# CheetahBooster.net
KiCad netlist of a schematic drawn in EAGLE
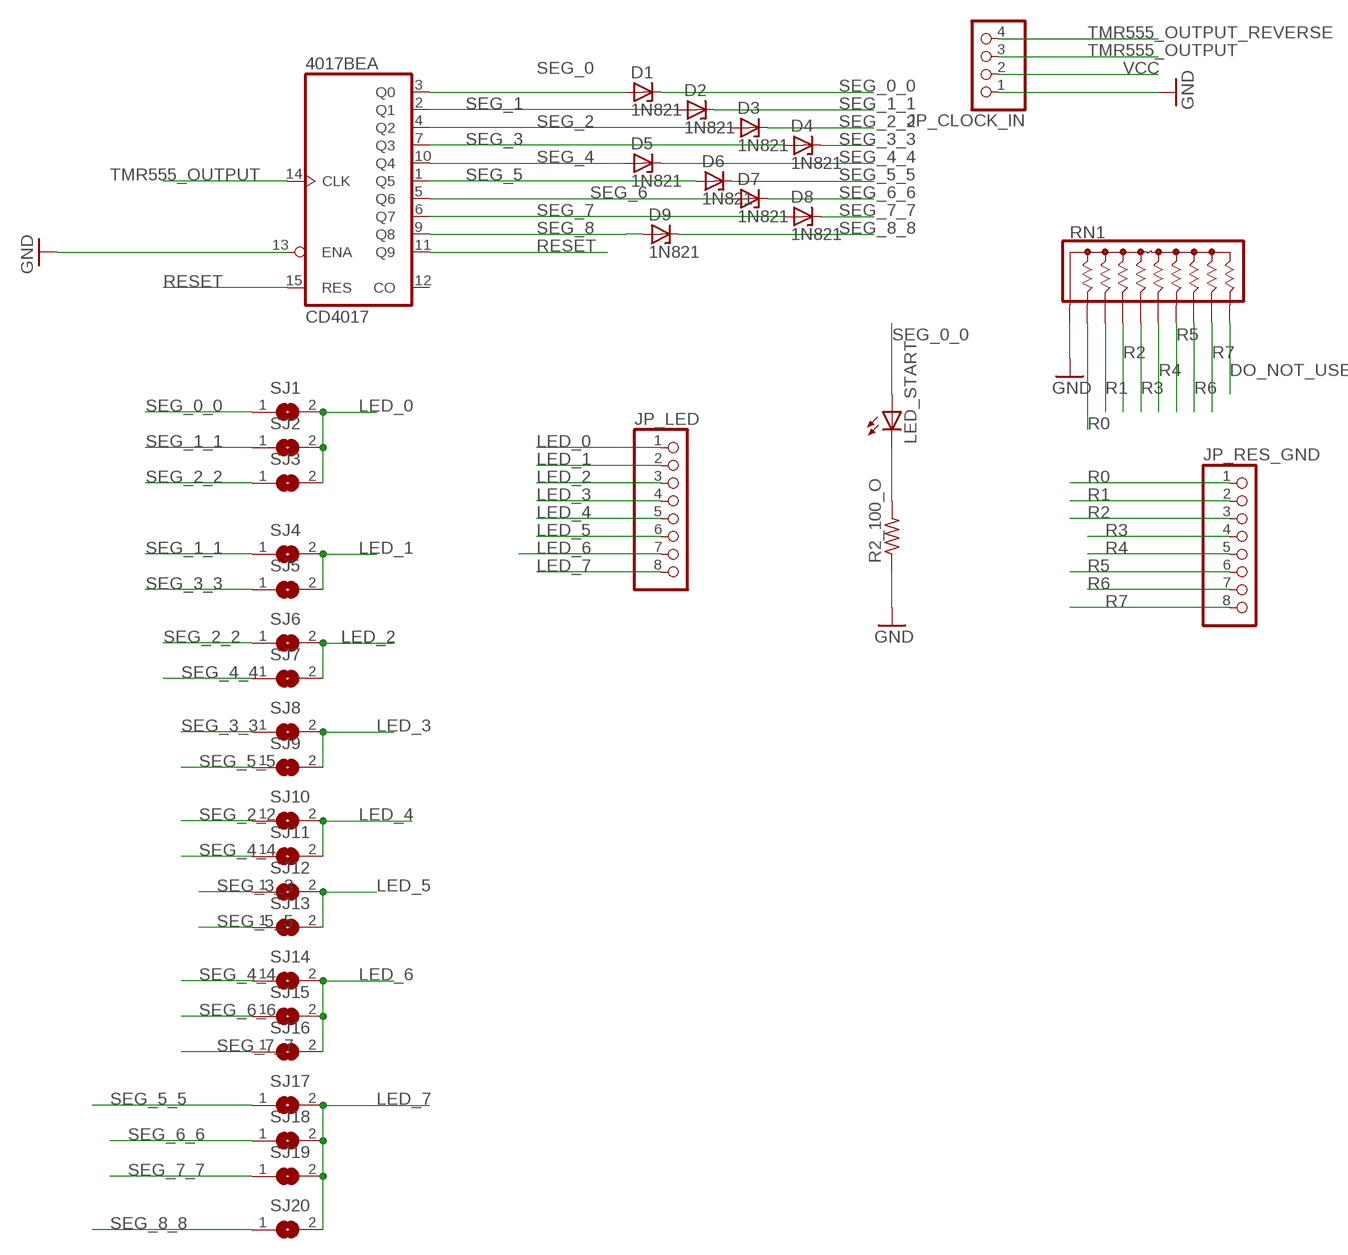
[diagram p0: schematic, sheet 1]

(export (version "E")
  (design (tool "Eeschema 10.0.6"))
  (components
    (comp (ref "4017BE")
      (value "CD4017")
      (footprint "eagle-import:DIL16")
      (libsource (lib "eagle-import") (part "CD4017"))
    )
    (comp (ref "D1")
      (value "1N821")
      (footprint "eagle-import:DO35Z10")
      (libsource (lib "eagle-import") (part "1N821"))
    )
    (comp (ref "D2")
      (value "1N821")
      (footprint "eagle-import:DO35Z10")
      (libsource (lib "eagle-import") (part "1N821"))
    )
    (comp (ref "D3")
      (value "1N821")
      (footprint "eagle-import:DO35Z10")
      (libsource (lib "eagle-import") (part "1N821"))
    )
    (comp (ref "D4")
      (value "1N821")
      (footprint "eagle-import:DO35Z10")
      (libsource (lib "eagle-import") (part "1N821"))
    )
    (comp (ref "D5")
      (value "1N821")
      (footprint "eagle-import:DO35Z10")
      (libsource (lib "eagle-import") (part "1N821"))
    )
    (comp (ref "D6")
      (value "1N821")
      (footprint "eagle-import:DO35Z10")
      (libsource (lib "eagle-import") (part "1N821"))
    )
    (comp (ref "D7")
      (value "1N821")
      (footprint "eagle-import:DO35Z10")
      (libsource (lib "eagle-import") (part "1N821"))
    )
    (comp (ref "D8")
      (value "1N821")
      (footprint "eagle-import:DO35Z10")
      (libsource (lib "eagle-import") (part "1N821"))
    )
    (comp (ref "D9")
      (value "1N821")
      (footprint "eagle-import:DO35Z10")
      (libsource (lib "eagle-import") (part "1N821"))
    )
    (comp (ref "JP_CLOCK_IN")
      (value "PINHD-1X4")
      (footprint "eagle-import:1X04")
      (libsource (lib "eagle-import") (part "PINHD-1X4"))
    )
    (comp (ref "JP_LED")
      (value "PINHD-1X8")
      (footprint "eagle-import:1X08")
      (libsource (lib "eagle-import") (part "PINHD-1X8"))
    )
    (comp (ref "JP_RES_GND")
      (value "PINHD-1X8")
      (footprint "eagle-import:1X08")
      (libsource (lib "eagle-import") (part "PINHD-1X8"))
    )
    (comp (ref "LED_START")
      (value "LEDSMT1206")
      (footprint "eagle-import:1206")
      (libsource (lib "eagle-import") (part "LEDSMT1206"))
    )
    (comp (ref "R2_100_O")
      (value "R-US_R1206")
      (footprint "eagle-import:R1206")
      (libsource (lib "eagle-import") (part "R-US_R1206"))
    )
    (comp (ref "RN1")
      (value "4610X")
      (footprint "eagle-import:SIP10")
      (libsource (lib "eagle-import") (part "4610X"))
    )
    (comp (ref "SJ1")
      (value "SOLDERJUMPER")
      (footprint "eagle-import:SOLDERJUMPER_ARROW_NOPASTE")
      (libsource (lib "eagle-import") (part "SOLDERJUMPER"))
    )
    (comp (ref "SJ2")
      (value "SOLDERJUMPER")
      (footprint "eagle-import:SOLDERJUMPER_ARROW_NOPASTE")
      (libsource (lib "eagle-import") (part "SOLDERJUMPER"))
    )
    (comp (ref "SJ3")
      (value "SOLDERJUMPER")
      (footprint "eagle-import:SOLDERJUMPER_ARROW_NOPASTE")
      (libsource (lib "eagle-import") (part "SOLDERJUMPER"))
    )
    (comp (ref "SJ4")
      (value "SOLDERJUMPER")
      (footprint "eagle-import:SOLDERJUMPER_ARROW_NOPASTE")
      (libsource (lib "eagle-import") (part "SOLDERJUMPER"))
    )
    (comp (ref "SJ5")
      (value "SOLDERJUMPER")
      (footprint "eagle-import:SOLDERJUMPER_ARROW_NOPASTE")
      (libsource (lib "eagle-import") (part "SOLDERJUMPER"))
    )
    (comp (ref "SJ6")
      (value "SOLDERJUMPER")
      (footprint "eagle-import:SOLDERJUMPER_ARROW_NOPASTE")
      (libsource (lib "eagle-import") (part "SOLDERJUMPER"))
    )
    (comp (ref "SJ7")
      (value "SOLDERJUMPER")
      (footprint "eagle-import:SOLDERJUMPER_ARROW_NOPASTE")
      (libsource (lib "eagle-import") (part "SOLDERJUMPER"))
    )
    (comp (ref "SJ8")
      (value "SOLDERJUMPER")
      (footprint "eagle-import:SOLDERJUMPER_ARROW_NOPASTE")
      (libsource (lib "eagle-import") (part "SOLDERJUMPER"))
    )
    (comp (ref "SJ9")
      (value "SOLDERJUMPER")
      (footprint "eagle-import:SOLDERJUMPER_ARROW_NOPASTE")
      (libsource (lib "eagle-import") (part "SOLDERJUMPER"))
    )
    (comp (ref "SJ10")
      (value "SOLDERJUMPER")
      (footprint "eagle-import:SOLDERJUMPER_ARROW_NOPASTE")
      (libsource (lib "eagle-import") (part "SOLDERJUMPER"))
    )
    (comp (ref "SJ11")
      (value "SOLDERJUMPER")
      (footprint "eagle-import:SOLDERJUMPER_ARROW_NOPASTE")
      (libsource (lib "eagle-import") (part "SOLDERJUMPER"))
    )
    (comp (ref "SJ12")
      (value "SOLDERJUMPER")
      (footprint "eagle-import:SOLDERJUMPER_ARROW_NOPASTE")
      (libsource (lib "eagle-import") (part "SOLDERJUMPER"))
    )
    (comp (ref "SJ13")
      (value "SOLDERJUMPER")
      (footprint "eagle-import:SOLDERJUMPER_ARROW_NOPASTE")
      (libsource (lib "eagle-import") (part "SOLDERJUMPER"))
    )
    (comp (ref "SJ14")
      (value "SOLDERJUMPER")
      (footprint "eagle-import:SOLDERJUMPER_ARROW_NOPASTE")
      (libsource (lib "eagle-import") (part "SOLDERJUMPER"))
    )
    (comp (ref "SJ15")
      (value "SOLDERJUMPER")
      (footprint "eagle-import:SOLDERJUMPER_ARROW_NOPASTE")
      (libsource (lib "eagle-import") (part "SOLDERJUMPER"))
    )
    (comp (ref "SJ16")
      (value "SOLDERJUMPER")
      (footprint "eagle-import:SOLDERJUMPER_ARROW_NOPASTE")
      (libsource (lib "eagle-import") (part "SOLDERJUMPER"))
    )
    (comp (ref "SJ17")
      (value "SOLDERJUMPER")
      (footprint "eagle-import:SOLDERJUMPER_ARROW_NOPASTE")
      (libsource (lib "eagle-import") (part "SOLDERJUMPER"))
    )
    (comp (ref "SJ18")
      (value "SOLDERJUMPER")
      (footprint "eagle-import:SOLDERJUMPER_ARROW_NOPASTE")
      (libsource (lib "eagle-import") (part "SOLDERJUMPER"))
    )
    (comp (ref "SJ19")
      (value "SOLDERJUMPER")
      (footprint "eagle-import:SOLDERJUMPER_ARROW_NOPASTE")
      (libsource (lib "eagle-import") (part "SOLDERJUMPER"))
    )
    (comp (ref "SJ20")
      (value "SOLDERJUMPER")
      (footprint "eagle-import:SOLDERJUMPER_ARROW_NOPASTE")
      (libsource (lib "eagle-import") (part "SOLDERJUMPER"))
    )
  )
  (nets
    (net (code "1") (name "/DO_NOT_USE") (class "Default")
      (node (ref "RN1") (pin "10") (pinfunction "10_10") (pintype "passive"))
    )
    (net (code "2") (name "/LED_0") (class "Default")
      (node (ref "JP_LED") (pin "1") (pinfunction "1_1") (pintype "passive"))
      (node (ref "SJ1") (pin "2") (pinfunction "2_2") (pintype "passive"))
      (node (ref "SJ2") (pin "2") (pinfunction "2_2") (pintype "passive"))
      (node (ref "SJ3") (pin "2") (pinfunction "2_2") (pintype "passive"))
    )
    (net (code "3") (name "/LED_1") (class "Default")
      (node (ref "JP_LED") (pin "2") (pinfunction "2_2") (pintype "passive"))
      (node (ref "SJ4") (pin "2") (pinfunction "2_2") (pintype "passive"))
      (node (ref "SJ5") (pin "2") (pinfunction "2_2") (pintype "passive"))
    )
    (net (code "4") (name "/LED_2") (class "Default")
      (node (ref "JP_LED") (pin "3") (pinfunction "3_3") (pintype "passive"))
      (node (ref "SJ6") (pin "2") (pinfunction "2_2") (pintype "passive"))
      (node (ref "SJ7") (pin "2") (pinfunction "2_2") (pintype "passive"))
    )
    (net (code "5") (name "/LED_3") (class "Default")
      (node (ref "JP_LED") (pin "4") (pinfunction "4_4") (pintype "passive"))
      (node (ref "SJ8") (pin "2") (pinfunction "2_2") (pintype "passive"))
      (node (ref "SJ9") (pin "2") (pinfunction "2_2") (pintype "passive"))
    )
    (net (code "6") (name "/LED_4") (class "Default")
      (node (ref "JP_LED") (pin "5") (pinfunction "5_5") (pintype "passive"))
      (node (ref "SJ10") (pin "2") (pinfunction "2_2") (pintype "passive"))
      (node (ref "SJ11") (pin "2") (pinfunction "2_2") (pintype "passive"))
    )
    (net (code "7") (name "/LED_5") (class "Default")
      (node (ref "JP_LED") (pin "6") (pinfunction "6_6") (pintype "passive"))
      (node (ref "SJ12") (pin "2") (pinfunction "2_2") (pintype "passive"))
      (node (ref "SJ13") (pin "2") (pinfunction "2_2") (pintype "passive"))
    )
    (net (code "8") (name "/LED_6") (class "Default")
      (node (ref "JP_LED") (pin "7") (pinfunction "7_7") (pintype "passive"))
      (node (ref "SJ14") (pin "2") (pinfunction "2_2") (pintype "passive"))
      (node (ref "SJ15") (pin "2") (pinfunction "2_2") (pintype "passive"))
      (node (ref "SJ16") (pin "2") (pinfunction "2_2") (pintype "passive"))
    )
    (net (code "9") (name "/LED_7") (class "Default")
      (node (ref "JP_LED") (pin "8") (pinfunction "8_8") (pintype "passive"))
      (node (ref "SJ17") (pin "2") (pinfunction "2_2") (pintype "passive"))
      (node (ref "SJ18") (pin "2") (pinfunction "2_2") (pintype "passive"))
      (node (ref "SJ19") (pin "2") (pinfunction "2_2") (pintype "passive"))
      (node (ref "SJ20") (pin "2") (pinfunction "2_2") (pintype "passive"))
    )
    (net (code "10") (name "/R0") (class "Default")
      (node (ref "JP_RES_GND") (pin "1") (pinfunction "1_1") (pintype "passive"))
      (node (ref "RN1") (pin "2") (pinfunction "2_2") (pintype "passive"))
    )
    (net (code "11") (name "/R1") (class "Default")
      (node (ref "JP_RES_GND") (pin "2") (pinfunction "2_2") (pintype "passive"))
      (node (ref "RN1") (pin "3") (pinfunction "3_3") (pintype "passive"))
    )
    (net (code "12") (name "/R2") (class "Default")
      (node (ref "JP_RES_GND") (pin "3") (pinfunction "3_3") (pintype "passive"))
      (node (ref "RN1") (pin "4") (pinfunction "4_4") (pintype "passive"))
    )
    (net (code "13") (name "/R3") (class "Default")
      (node (ref "JP_RES_GND") (pin "4") (pinfunction "4_4") (pintype "passive"))
      (node (ref "RN1") (pin "5") (pinfunction "5_5") (pintype "passive"))
    )
    (net (code "14") (name "/R4") (class "Default")
      (node (ref "JP_RES_GND") (pin "5") (pinfunction "5_5") (pintype "passive"))
      (node (ref "RN1") (pin "6") (pinfunction "6_6") (pintype "passive"))
    )
    (net (code "15") (name "/R5") (class "Default")
      (node (ref "JP_RES_GND") (pin "6") (pinfunction "6_6") (pintype "passive"))
      (node (ref "RN1") (pin "7") (pinfunction "7_7") (pintype "passive"))
    )
    (net (code "16") (name "/R6") (class "Default")
      (node (ref "JP_RES_GND") (pin "7") (pinfunction "7_7") (pintype "passive"))
      (node (ref "RN1") (pin "8") (pinfunction "8_8") (pintype "passive"))
    )
    (net (code "17") (name "/R7") (class "Default")
      (node (ref "JP_RES_GND") (pin "8") (pinfunction "8_8") (pintype "passive"))
      (node (ref "RN1") (pin "9") (pinfunction "9_9") (pintype "passive"))
    )
    (net (code "18") (name "/RESET") (class "Default")
      (node (ref "4017BE") (pin "11") (pinfunction "Q9_11") (pintype "output"))
      (node (ref "4017BE") (pin "15") (pinfunction "RES_15") (pintype "input"))
    )
    (net (code "19") (name "/SEG_0") (class "Default")
      (node (ref "4017BE") (pin "3") (pinfunction "Q0_3") (pintype "output"))
      (node (ref "D1") (pin "A") (pinfunction "A_A") (pintype "passive"))
    )
    (net (code "20") (name "/SEG_0_0") (class "Default")
      (node (ref "D1") (pin "C") (pinfunction "C_C") (pintype "passive"))
      (node (ref "LED_START") (pin "A") (pinfunction "A_A") (pintype "passive"))
      (node (ref "SJ1") (pin "1") (pinfunction "1_1") (pintype "passive"))
    )
    (net (code "21") (name "/SEG_1") (class "Default")
      (node (ref "4017BE") (pin "2") (pinfunction "Q1_2") (pintype "output"))
      (node (ref "D2") (pin "A") (pinfunction "A_A") (pintype "passive"))
    )
    (net (code "22") (name "/SEG_1_1") (class "Default")
      (node (ref "D2") (pin "C") (pinfunction "C_C") (pintype "passive"))
      (node (ref "SJ2") (pin "1") (pinfunction "1_1") (pintype "passive"))
      (node (ref "SJ4") (pin "1") (pinfunction "1_1") (pintype "passive"))
    )
    (net (code "23") (name "/SEG_2") (class "Default")
      (node (ref "4017BE") (pin "4") (pinfunction "Q2_4") (pintype "output"))
      (node (ref "D3") (pin "A") (pinfunction "A_A") (pintype "passive"))
    )
    (net (code "24") (name "/SEG_2_2") (class "Default")
      (node (ref "D3") (pin "C") (pinfunction "C_C") (pintype "passive"))
      (node (ref "SJ10") (pin "1") (pinfunction "1_1") (pintype "passive"))
      (node (ref "SJ3") (pin "1") (pinfunction "1_1") (pintype "passive"))
      (node (ref "SJ6") (pin "1") (pinfunction "1_1") (pintype "passive"))
    )
    (net (code "25") (name "/SEG_3") (class "Default")
      (node (ref "4017BE") (pin "7") (pinfunction "Q3_7") (pintype "output"))
      (node (ref "D4") (pin "A") (pinfunction "A_A") (pintype "passive"))
    )
    (net (code "26") (name "/SEG_3_3") (class "Default")
      (node (ref "D4") (pin "C") (pinfunction "C_C") (pintype "passive"))
      (node (ref "SJ12") (pin "1") (pinfunction "1_1") (pintype "passive"))
      (node (ref "SJ5") (pin "1") (pinfunction "1_1") (pintype "passive"))
      (node (ref "SJ8") (pin "1") (pinfunction "1_1") (pintype "passive"))
    )
    (net (code "27") (name "/SEG_4") (class "Default")
      (node (ref "4017BE") (pin "10") (pinfunction "Q4_10") (pintype "output"))
      (node (ref "D5") (pin "A") (pinfunction "A_A") (pintype "passive"))
    )
    (net (code "28") (name "/SEG_4_4") (class "Default")
      (node (ref "D5") (pin "C") (pinfunction "C_C") (pintype "passive"))
      (node (ref "SJ11") (pin "1") (pinfunction "1_1") (pintype "passive"))
      (node (ref "SJ14") (pin "1") (pinfunction "1_1") (pintype "passive"))
      (node (ref "SJ7") (pin "1") (pinfunction "1_1") (pintype "passive"))
    )
    (net (code "29") (name "/SEG_5") (class "Default")
      (node (ref "4017BE") (pin "1") (pinfunction "Q5_1") (pintype "output"))
      (node (ref "D6") (pin "A") (pinfunction "A_A") (pintype "passive"))
    )
    (net (code "30") (name "/SEG_5_5") (class "Default")
      (node (ref "D6") (pin "C") (pinfunction "C_C") (pintype "passive"))
      (node (ref "SJ13") (pin "1") (pinfunction "1_1") (pintype "passive"))
      (node (ref "SJ17") (pin "1") (pinfunction "1_1") (pintype "passive"))
      (node (ref "SJ9") (pin "1") (pinfunction "1_1") (pintype "passive"))
    )
    (net (code "31") (name "/SEG_6") (class "Default")
      (node (ref "4017BE") (pin "5") (pinfunction "Q6_5") (pintype "output"))
      (node (ref "D7") (pin "A") (pinfunction "A_A") (pintype "passive"))
    )
    (net (code "32") (name "/SEG_6_6") (class "Default")
      (node (ref "D7") (pin "C") (pinfunction "C_C") (pintype "passive"))
      (node (ref "SJ15") (pin "1") (pinfunction "1_1") (pintype "passive"))
      (node (ref "SJ18") (pin "1") (pinfunction "1_1") (pintype "passive"))
    )
    (net (code "33") (name "/SEG_7") (class "Default")
      (node (ref "4017BE") (pin "6") (pinfunction "Q7_6") (pintype "output"))
      (node (ref "D8") (pin "A") (pinfunction "A_A") (pintype "passive"))
    )
    (net (code "34") (name "/SEG_7_7") (class "Default")
      (node (ref "D8") (pin "C") (pinfunction "C_C") (pintype "passive"))
      (node (ref "SJ16") (pin "1") (pinfunction "1_1") (pintype "passive"))
      (node (ref "SJ19") (pin "1") (pinfunction "1_1") (pintype "passive"))
    )
    (net (code "35") (name "/SEG_8") (class "Default")
      (node (ref "4017BE") (pin "9") (pinfunction "Q8_9") (pintype "output"))
      (node (ref "D9") (pin "A") (pinfunction "A_A") (pintype "passive"))
    )
    (net (code "36") (name "/SEG_8_8") (class "Default")
      (node (ref "D9") (pin "C") (pinfunction "C_C") (pintype "passive"))
      (node (ref "SJ20") (pin "1") (pinfunction "1_1") (pintype "passive"))
    )
    (net (code "37") (name "/TMR555_OUTPUT") (class "Default")
      (node (ref "4017BE") (pin "14") (pinfunction "CLK_14") (pintype "input"))
      (node (ref "JP_CLOCK_IN") (pin "3") (pinfunction "3_3") (pintype "passive"))
    )
    (net (code "38") (name "/TMR555_OUTPUT_REVERSE") (class "Default")
      (node (ref "JP_CLOCK_IN") (pin "4") (pinfunction "4_4") (pintype "passive"))
    )
    (net (code "39") (name "/VCC") (class "Default")
      (node (ref "JP_CLOCK_IN") (pin "2") (pinfunction "2_2") (pintype "passive"))
    )
    (net (code "40") (name "GND") (class "Default")
      (node (ref "4017BE") (pin "13") (pinfunction "ENA_13") (pintype "input"))
      (node (ref "JP_CLOCK_IN") (pin "1") (pinfunction "1_1") (pintype "passive"))
      (node (ref "R2_100_O") (pin "1") (pinfunction "1_1") (pintype "passive"))
      (node (ref "RN1") (pin "1") (pinfunction "1_1") (pintype "passive"))
    )
    (net (code "41") (name "Net-(LED_START-PadC)") (class "Default")
      (node (ref "LED_START") (pin "C") (pinfunction "C_C") (pintype "passive"))
      (node (ref "R2_100_O") (pin "2") (pinfunction "2_2") (pintype "passive"))
    )
    (net (code "42") (name "unconnected-(4017BEA-CO-Pad12)") (class "Default")
      (node (ref "4017BE") (pin "12") (pinfunction "CO_12") (pintype "output"))
    )
  )
)
